# Klon.net
KiCad netlist of a schematic drawn in EAGLE
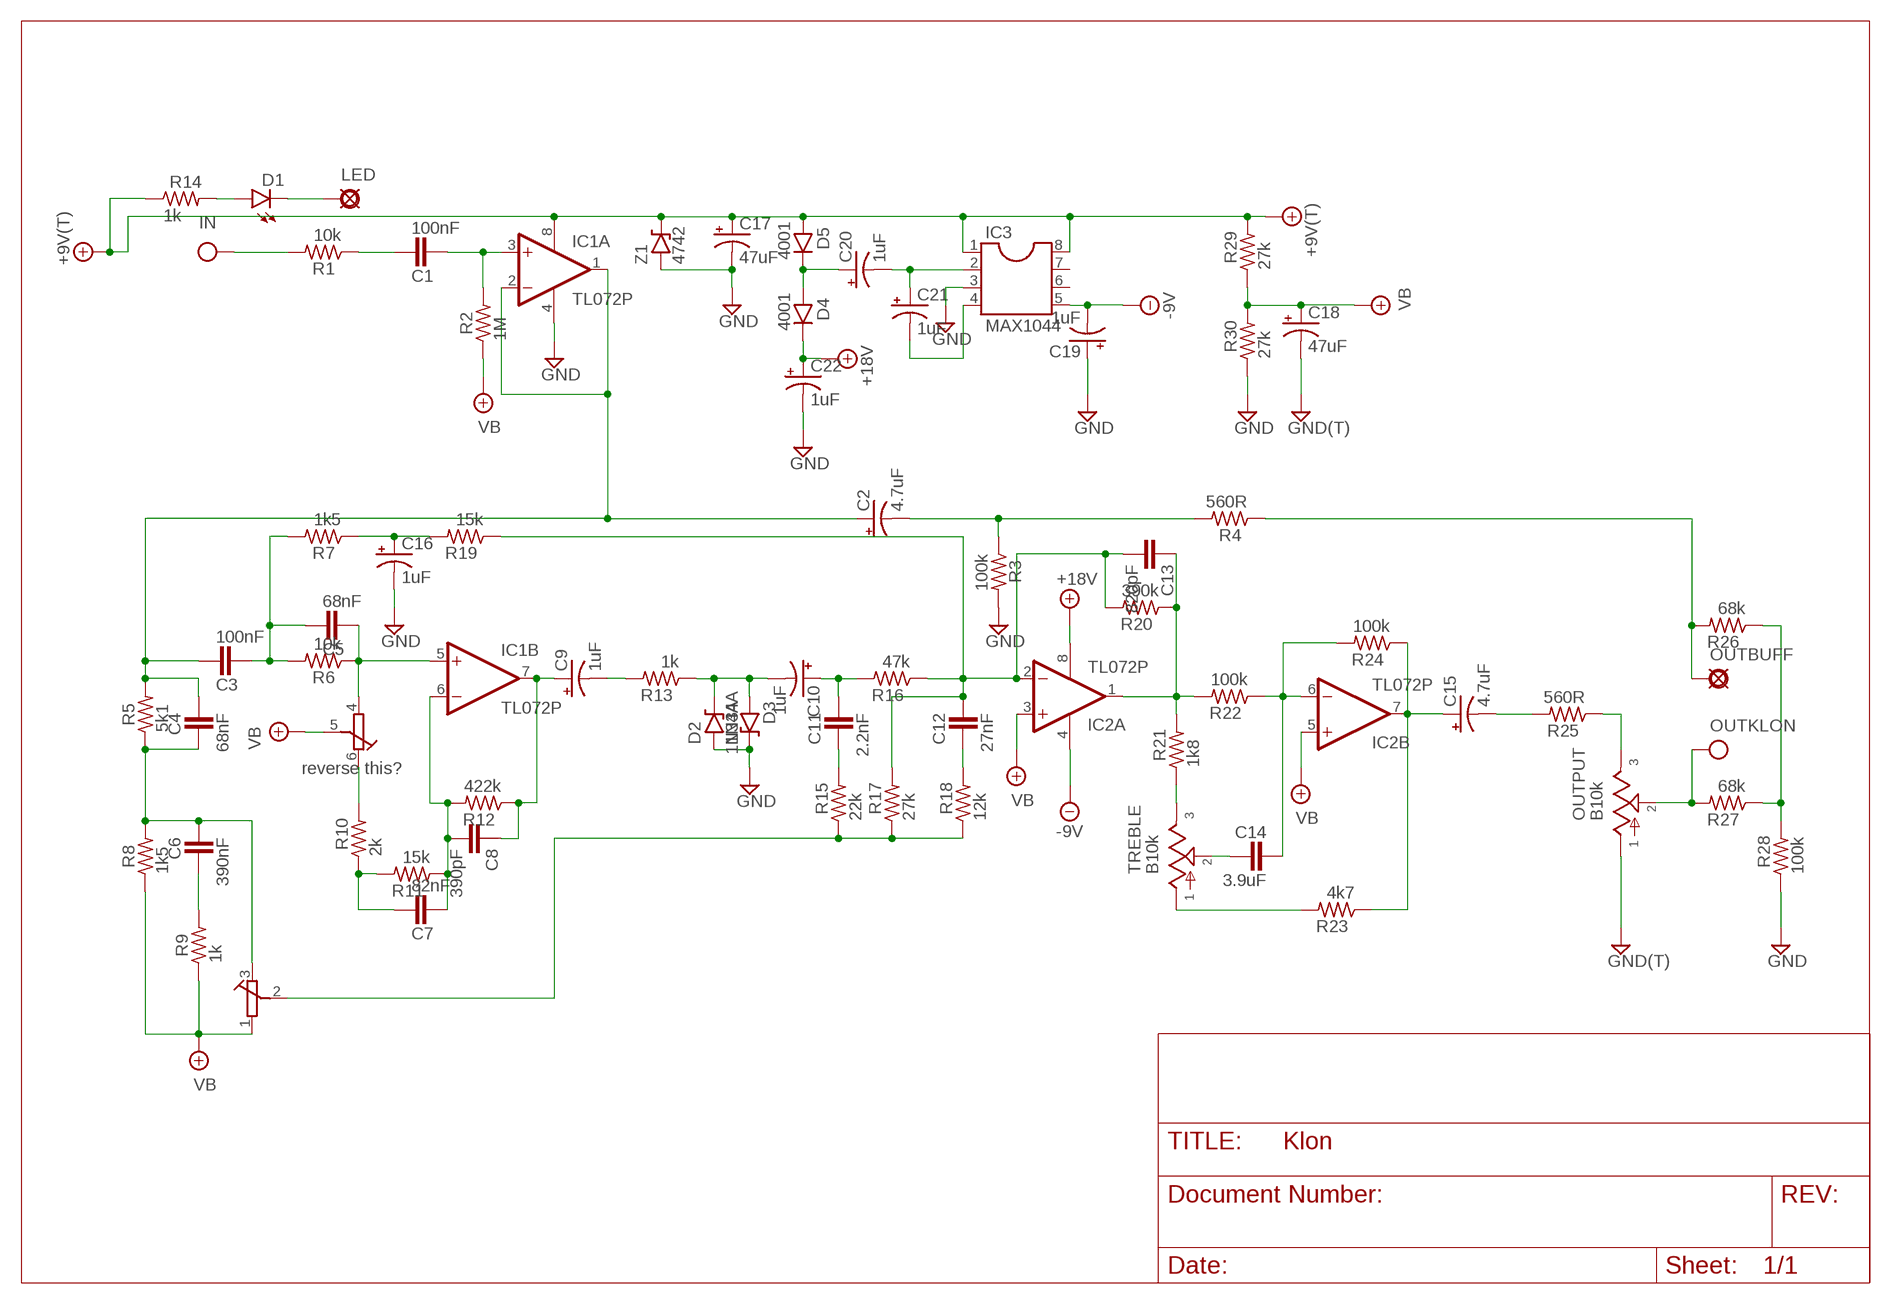
[diagram p0: schematic, sheet 1]

(export (version "E")
  (design (tool "Eeschema 10.0.6"))
  (components
    (comp (ref "+9V")
      (value "+9V(T)")
      (footprint "eagle-import:SQUARE")
      (libsource (lib "eagle-import") (part "+9V(T)"))
    )
    (comp (ref "+9V1")
      (value "+9V(T)")
      (footprint "eagle-import:SQUARE")
      (libsource (lib "eagle-import") (part "+9V(T)"))
    )
    (comp (ref "C1")
      (value "100nF")
      (footprint "eagle-import:072X025")
      (libsource (lib "eagle-import") (part "072X0252"))
    )
    (comp (ref "C2")
      (value "4.7uF")
      (footprint "eagle-import:050_020_1")
      (libsource (lib "eagle-import") (part "0501"))
    )
    (comp (ref "C3")
      (value "100nF")
      (footprint "eagle-import:072X025")
      (libsource (lib "eagle-import") (part "072X0252"))
    )
    (comp (ref "C4")
      (value "68nF")
      (footprint "eagle-import:072X025")
      (libsource (lib "eagle-import") (part "072X0252"))
    )
    (comp (ref "C5")
      (value "68nF")
      (footprint "eagle-import:072X025")
      (libsource (lib "eagle-import") (part "072X0252"))
    )
    (comp (ref "C6")
      (value "390nF")
      (footprint "eagle-import:072X025")
      (libsource (lib "eagle-import") (part "072X0252"))
    )
    (comp (ref "C7")
      (value "82nF")
      (footprint "eagle-import:072X025")
      (libsource (lib "eagle-import") (part "072X0252"))
    )
    (comp (ref "C8")
      (value "390pF")
      (footprint "eagle-import:050X030_025")
      (libsource (lib "eagle-import") (part "050X030_0251"))
    )
    (comp (ref "C9")
      (value "1uF")
      (footprint "eagle-import:050_020_1")
      (libsource (lib "eagle-import") (part "0501"))
    )
    (comp (ref "C10")
      (value "1uF")
      (footprint "eagle-import:050_020_1")
      (libsource (lib "eagle-import") (part "0501"))
    )
    (comp (ref "C11")
      (value "2.2nF")
      (footprint "eagle-import:072X025")
      (libsource (lib "eagle-import") (part "072X0252"))
    )
    (comp (ref "C12")
      (value "27nF")
      (footprint "eagle-import:072X025")
      (libsource (lib "eagle-import") (part "072X0252"))
    )
    (comp (ref "C13")
      (value "820pF")
      (footprint "eagle-import:050X030_025")
      (libsource (lib "eagle-import") (part "050X030_0251"))
    )
    (comp (ref "C14")
      (value "3.9uF")
      (footprint "eagle-import:072X025")
      (libsource (lib "eagle-import") (part "072X0252"))
    )
    (comp (ref "C15")
      (value "4.7uF")
      (footprint "eagle-import:050_020_1")
      (libsource (lib "eagle-import") (part "0501"))
    )
    (comp (ref "C16")
      (value "1uF")
      (footprint "eagle-import:050_020_1")
      (libsource (lib "eagle-import") (part "0501"))
    )
    (comp (ref "C17")
      (value "47uF")
      (footprint "eagle-import:063_025")
      (libsource (lib "eagle-import") (part "0631"))
    )
    (comp (ref "C18")
      (value "47uF")
      (footprint "eagle-import:063_025")
      (libsource (lib "eagle-import") (part "0631"))
    )
    (comp (ref "C19")
      (value "1uF")
      (footprint "eagle-import:050_020_1")
      (libsource (lib "eagle-import") (part "0501"))
    )
    (comp (ref "C20")
      (value "1uF")
      (footprint "eagle-import:050_020_1")
      (libsource (lib "eagle-import") (part "0501"))
    )
    (comp (ref "C21")
      (value "1uF")
      (footprint "eagle-import:050_020_1")
      (libsource (lib "eagle-import") (part "0501"))
    )
    (comp (ref "C22")
      (value "1uF")
      (footprint "eagle-import:050_020_1")
      (libsource (lib "eagle-import") (part "0501"))
    )
    (comp (ref "D1")
      (value "LED")
      (footprint "eagle-import:LED3MM")
      (libsource (lib "eagle-import") (part "LED3MM"))
    )
    (comp (ref "D2")
      (value "1N34A")
      (footprint "eagle-import:DO35-3")
      (libsource (lib "eagle-import") (part "1N9ZENER"))
    )
    (comp (ref "D3")
      (value "1N34A")
      (footprint "eagle-import:DO35-3")
      (libsource (lib "eagle-import") (part "1N9ZENER"))
    )
    (comp (ref "D4")
      (value "4001")
      (footprint "eagle-import:DO41-3")
      (libsource (lib "eagle-import") (part "1N400X.3"))
    )
    (comp (ref "D5")
      (value "4001")
      (footprint "eagle-import:DO41-3")
      (libsource (lib "eagle-import") (part "1N400X.3"))
    )
    (comp (ref "G")
      (value "GND(T)")
      (footprint "eagle-import:SQUARE")
      (libsource (lib "eagle-import") (part "GND(T)"))
    )
    (comp (ref "G1")
      (value "GND(T)")
      (footprint "eagle-import:SQUARE")
      (libsource (lib "eagle-import") (part "GND(T)"))
    )
    (comp (ref "GAIN")
      (value "B100k")
      (footprint "eagle-import:ALPHA16MM")
      (libsource (lib "eagle-import") (part "ALPHA16MM"))
    )
    (comp (ref "IC1")
      (value "TL072P")
      (footprint "eagle-import:DIL08")
      (libsource (lib "eagle-import") (part "TL072P"))
    )
    (comp (ref "IC2")
      (value "TL072P")
      (footprint "eagle-import:DIL08")
      (libsource (lib "eagle-import") (part "TL072P"))
    )
    (comp (ref "IC3")
      (value "MAX1044")
      (footprint "eagle-import:DIL08")
      (libsource (lib "eagle-import") (part "MAX1044"))
    )
    (comp (ref "IN")
      (value "IN(T)")
      (footprint "eagle-import:SQUARE")
      (libsource (lib "eagle-import") (part "IN(T)"))
    )
    (comp (ref "LED")
      (value "PAD")
      (footprint "eagle-import:SQUARE")
      (libsource (lib "eagle-import") (part "PAD"))
    )
    (comp (ref "OUTBUFF")
      (value "PAD")
      (footprint "eagle-import:SQUARE")
      (libsource (lib "eagle-import") (part "PAD"))
    )
    (comp (ref "OUTKLON")
      (value "OUT(T)")
      (footprint "eagle-import:SQUARE")
      (libsource (lib "eagle-import") (part "OUT(T)"))
    )
    (comp (ref "OUTPUT")
      (value "B10k")
      (footprint "eagle-import:16MM")
      (libsource (lib "eagle-import") (part "POT16MM"))
    )
    (comp (ref "R1")
      (value "10k")
      (footprint "eagle-import:R0207_3")
      (libsource (lib "eagle-import") (part "6MM.3"))
    )
    (comp (ref "R2")
      (value "1M")
      (footprint "eagle-import:R0207_3")
      (libsource (lib "eagle-import") (part "6MM.3"))
    )
    (comp (ref "R3")
      (value "100k")
      (footprint "eagle-import:R0207_3")
      (libsource (lib "eagle-import") (part "6MM.3"))
    )
    (comp (ref "R4")
      (value "560R")
      (footprint "eagle-import:R0207_3")
      (libsource (lib "eagle-import") (part "6MM.3"))
    )
    (comp (ref "R5")
      (value "5k1")
      (footprint "eagle-import:R0207_3")
      (libsource (lib "eagle-import") (part "6MM.3"))
    )
    (comp (ref "R6")
      (value "10k")
      (footprint "eagle-import:R0207_3")
      (libsource (lib "eagle-import") (part "6MM.3"))
    )
    (comp (ref "R7")
      (value "1k5")
      (footprint "eagle-import:R0207_3")
      (libsource (lib "eagle-import") (part "6MM.3"))
    )
    (comp (ref "R8")
      (value "1k5")
      (footprint "eagle-import:R0207_3")
      (libsource (lib "eagle-import") (part "6MM.3"))
    )
    (comp (ref "R9")
      (value "1k")
      (footprint "eagle-import:R0207_3")
      (libsource (lib "eagle-import") (part "6MM.3"))
    )
    (comp (ref "R10")
      (value "2k")
      (footprint "eagle-import:R0207_3")
      (libsource (lib "eagle-import") (part "6MM.3"))
    )
    (comp (ref "R11")
      (value "15k")
      (footprint "eagle-import:R0207_3")
      (libsource (lib "eagle-import") (part "6MM.3"))
    )
    (comp (ref "R12")
      (value "422k")
      (footprint "eagle-import:R0207_3")
      (libsource (lib "eagle-import") (part "6MM.3"))
    )
    (comp (ref "R13")
      (value "1k")
      (footprint "eagle-import:R0207_3")
      (libsource (lib "eagle-import") (part "6MM.3"))
    )
    (comp (ref "R14")
      (value "1k")
      (footprint "eagle-import:R0207_3")
      (libsource (lib "eagle-import") (part "6MM.3"))
    )
    (comp (ref "R15")
      (value "22k")
      (footprint "eagle-import:R0207_3")
      (libsource (lib "eagle-import") (part "6MM.3"))
    )
    (comp (ref "R16")
      (value "47k")
      (footprint "eagle-import:R0207_3")
      (libsource (lib "eagle-import") (part "6MM.3"))
    )
    (comp (ref "R17")
      (value "27k")
      (footprint "eagle-import:R0207_3")
      (libsource (lib "eagle-import") (part "6MM.3"))
    )
    (comp (ref "R18")
      (value "12k")
      (footprint "eagle-import:R0207_3")
      (libsource (lib "eagle-import") (part "6MM.3"))
    )
    (comp (ref "R19")
      (value "15k")
      (footprint "eagle-import:R0207_3")
      (libsource (lib "eagle-import") (part "6MM.3"))
    )
    (comp (ref "R20")
      (value "390k")
      (footprint "eagle-import:R0207_3")
      (libsource (lib "eagle-import") (part "6MM.3"))
    )
    (comp (ref "R21")
      (value "1k8")
      (footprint "eagle-import:R0207_3")
      (libsource (lib "eagle-import") (part "6MM.3"))
    )
    (comp (ref "R22")
      (value "100k")
      (footprint "eagle-import:R0207_3")
      (libsource (lib "eagle-import") (part "6MM.3"))
    )
    (comp (ref "R23")
      (value "4k7")
      (footprint "eagle-import:R0207_3")
      (libsource (lib "eagle-import") (part "6MM.3"))
    )
    (comp (ref "R24")
      (value "100k")
      (footprint "eagle-import:R0207_3")
      (libsource (lib "eagle-import") (part "6MM.3"))
    )
    (comp (ref "R25")
      (value "560R")
      (footprint "eagle-import:R0207_3")
      (libsource (lib "eagle-import") (part "6MM.3"))
    )
    (comp (ref "R26")
      (value "68k")
      (footprint "eagle-import:R0207_3")
      (libsource (lib "eagle-import") (part "6MM.3"))
    )
    (comp (ref "R27")
      (value "68k")
      (footprint "eagle-import:R0207_3")
      (libsource (lib "eagle-import") (part "6MM.3"))
    )
    (comp (ref "R28")
      (value "100k")
      (footprint "eagle-import:R0207_3")
      (libsource (lib "eagle-import") (part "6MM.3"))
    )
    (comp (ref "R29")
      (value "27k")
      (footprint "eagle-import:R0207_3")
      (libsource (lib "eagle-import") (part "6MM.3"))
    )
    (comp (ref "R30")
      (value "27k")
      (footprint "eagle-import:R0207_3")
      (libsource (lib "eagle-import") (part "6MM.3"))
    )
    (comp (ref "TREBLE")
      (value "B10k")
      (footprint "eagle-import:16MM")
      (libsource (lib "eagle-import") (part "POT16MM"))
    )
    (comp (ref "Z1")
      (value "4742")
      (footprint "eagle-import:DO41-3")
      (libsource (lib "eagle-import") (part "1N47XX3"))
    )
  )
  (nets
    (net (code "1") (name "+9V(T)") (class "Default")
      (node (ref "+9V") (pin "1") (pinfunction "+9V_1") (pintype "power_in"))
      (node (ref "+9V1") (pin "1") (pinfunction "+9V_1") (pintype "power_in"))
      (node (ref "C17") (pin "+") (pinfunction "+_+") (pintype "passive"))
      (node (ref "D5") (pin "A") (pinfunction "A_A") (pintype "passive"))
      (node (ref "IC1") (pin "8") (pinfunction "V+_8") (pintype "power_in"))
      (node (ref "IC3") (pin "1") (pinfunction "1_1") (pintype "passive"))
      (node (ref "IC3") (pin "8") (pinfunction "8_8") (pintype "passive"))
      (node (ref "R14") (pin "1") (pinfunction "1_1") (pintype "passive"))
      (node (ref "R29") (pin "2") (pinfunction "2_2") (pintype "passive"))
      (node (ref "Z1") (pin "C") (pinfunction "C_C") (pintype "passive"))
    )
    (net (code "2") (name "+18V") (class "Default")
      (node (ref "C22") (pin "+") (pinfunction "+_+") (pintype "passive"))
      (node (ref "D4") (pin "C") (pinfunction "C_C") (pintype "passive"))
      (node (ref "IC2") (pin "8") (pinfunction "V+_8") (pintype "power_in"))
    )
    (net (code "3") (name "-9V") (class "Default")
      (node (ref "C19") (pin "-") (pinfunction "-_-") (pintype "passive"))
      (node (ref "IC2") (pin "4") (pinfunction "V-_4") (pintype "power_in"))
      (node (ref "IC3") (pin "5") (pinfunction "5_5") (pintype "passive"))
    )
    (net (code "4") (name "GND") (class "Default")
      (node (ref "C16") (pin "-") (pinfunction "-_-") (pintype "passive"))
      (node (ref "C17") (pin "-") (pinfunction "-_-") (pintype "passive"))
      (node (ref "C18") (pin "-") (pinfunction "-_-") (pintype "passive"))
      (node (ref "C19") (pin "+") (pinfunction "+_+") (pintype "passive"))
      (node (ref "C22") (pin "-") (pinfunction "-_-") (pintype "passive"))
      (node (ref "D2") (pin "A") (pinfunction "A_A") (pintype "passive"))
      (node (ref "D3") (pin "C") (pinfunction "C_C") (pintype "passive"))
      (node (ref "G") (pin "1") (pinfunction "GND_1") (pintype "power_in"))
      (node (ref "G1") (pin "1") (pinfunction "GND_1") (pintype "power_in"))
      (node (ref "IC1") (pin "4") (pinfunction "V-_4") (pintype "power_in"))
      (node (ref "IC3") (pin "3") (pinfunction "3_3") (pintype "passive"))
      (node (ref "OUTPUT") (pin "1") (pinfunction "1_1") (pintype "passive"))
      (node (ref "R28") (pin "1") (pinfunction "1_1") (pintype "passive"))
      (node (ref "R3") (pin "2") (pinfunction "2_2") (pintype "passive"))
      (node (ref "R30") (pin "1") (pinfunction "1_1") (pintype "passive"))
      (node (ref "Z1") (pin "A") (pinfunction "A_A") (pintype "passive"))
    )
    (net (code "5") (name "IN(T)") (class "Default")
      (node (ref "IN") (pin "1") (pinfunction "IN_1") (pintype "power_in"))
      (node (ref "R1") (pin "2") (pinfunction "2_2") (pintype "passive"))
    )
    (net (code "6") (name "Net-(C1-Pad2)") (class "Default")
      (node (ref "C1") (pin "2") (pinfunction "2_2") (pintype "passive"))
      (node (ref "R1") (pin "1") (pinfunction "1_1") (pintype "passive"))
    )
    (net (code "7") (name "Net-(C2-Pad-)") (class "Default")
      (node (ref "C2") (pin "-") (pinfunction "-_-") (pintype "passive"))
      (node (ref "R3") (pin "1") (pinfunction "1_1") (pintype "passive"))
      (node (ref "R4") (pin "2") (pinfunction "2_2") (pintype "passive"))
    )
    (net (code "8") (name "Net-(C3-Pad1)") (class "Default")
      (node (ref "C3") (pin "1") (pinfunction "1_1") (pintype "passive"))
      (node (ref "C5") (pin "2") (pinfunction "2_2") (pintype "passive"))
      (node (ref "R6") (pin "2") (pinfunction "2_2") (pintype "passive"))
      (node (ref "R7") (pin "2") (pinfunction "2_2") (pintype "passive"))
    )
    (net (code "9") (name "Net-(C6-Pad1)") (class "Default")
      (node (ref "C6") (pin "1") (pinfunction "1_1") (pintype "passive"))
      (node (ref "R9") (pin "2") (pinfunction "2_2") (pintype "passive"))
    )
    (net (code "10") (name "Net-(C7-Pad2)") (class "Default")
      (node (ref "C7") (pin "2") (pinfunction "2_2") (pintype "passive"))
      (node (ref "R10") (pin "1") (pinfunction "1_1") (pintype "passive"))
      (node (ref "R11") (pin "2") (pinfunction "2_2") (pintype "passive"))
    )
    (net (code "11") (name "Net-(C9-Pad-)") (class "Default")
      (node (ref "C9") (pin "-") (pinfunction "-_-") (pintype "passive"))
      (node (ref "R13") (pin "2") (pinfunction "2_2") (pintype "passive"))
    )
    (net (code "12") (name "Net-(C10-Pad+)") (class "Default")
      (node (ref "C10") (pin "+") (pinfunction "+_+") (pintype "passive"))
      (node (ref "C11") (pin "2") (pinfunction "2_2") (pintype "passive"))
      (node (ref "R16") (pin "2") (pinfunction "2_2") (pintype "passive"))
    )
    (net (code "13") (name "Net-(C10-Pad-)") (class "Default")
      (node (ref "C10") (pin "-") (pinfunction "-_-") (pintype "passive"))
      (node (ref "D2") (pin "C") (pinfunction "C_C") (pintype "passive"))
      (node (ref "D3") (pin "A") (pinfunction "A_A") (pintype "passive"))
      (node (ref "R13") (pin "1") (pinfunction "1_1") (pintype "passive"))
    )
    (net (code "14") (name "Net-(C11-Pad1)") (class "Default")
      (node (ref "C11") (pin "1") (pinfunction "1_1") (pintype "passive"))
      (node (ref "R15") (pin "2") (pinfunction "2_2") (pintype "passive"))
    )
    (net (code "15") (name "Net-(C12-Pad1)") (class "Default")
      (node (ref "C12") (pin "1") (pinfunction "1_1") (pintype "passive"))
      (node (ref "R18") (pin "2") (pinfunction "2_2") (pintype "passive"))
    )
    (net (code "16") (name "Net-(C14-Pad1)") (class "Default")
      (node (ref "C14") (pin "1") (pinfunction "1_1") (pintype "passive"))
      (node (ref "TREBLE") (pin "2") (pinfunction "2_2") (pintype "passive"))
    )
    (net (code "17") (name "Net-(C15-Pad-)") (class "Default")
      (node (ref "C15") (pin "-") (pinfunction "-_-") (pintype "passive"))
      (node (ref "R25") (pin "2") (pinfunction "2_2") (pintype "passive"))
    )
    (net (code "18") (name "Net-(C16-Pad+)") (class "Default")
      (node (ref "C16") (pin "+") (pinfunction "+_+") (pintype "passive"))
      (node (ref "R19") (pin "2") (pinfunction "2_2") (pintype "passive"))
      (node (ref "R7") (pin "1") (pinfunction "1_1") (pintype "passive"))
    )
    (net (code "19") (name "Net-(C20-Pad+)") (class "Default")
      (node (ref "C20") (pin "+") (pinfunction "+_+") (pintype "passive"))
      (node (ref "D4") (pin "A") (pinfunction "A_A") (pintype "passive"))
      (node (ref "D5") (pin "C") (pinfunction "C_C") (pintype "passive"))
    )
    (net (code "20") (name "Net-(C20-Pad-)") (class "Default")
      (node (ref "C20") (pin "-") (pinfunction "-_-") (pintype "passive"))
      (node (ref "C21") (pin "+") (pinfunction "+_+") (pintype "passive"))
      (node (ref "IC3") (pin "2") (pinfunction "2_2") (pintype "passive"))
    )
    (net (code "21") (name "Net-(C21-Pad-)") (class "Default")
      (node (ref "C21") (pin "-") (pinfunction "-_-") (pintype "passive"))
      (node (ref "IC3") (pin "4") (pinfunction "4_4") (pintype "passive"))
    )
    (net (code "22") (name "Net-(D1-C)") (class "Default")
      (node (ref "D1") (pin "K") (pinfunction "C_K") (pintype "passive"))
      (node (ref "LED") (pin "1") (pinfunction "PAD_1") (pintype "passive"))
    )
    (net (code "23") (name "Net-(D1-PadA)") (class "Default")
      (node (ref "D1") (pin "A") (pinfunction "A_A") (pintype "passive"))
      (node (ref "R14") (pin "2") (pinfunction "2_2") (pintype "passive"))
    )
    (net (code "24") (name "Net-(GAINA-IN)") (class "Default")
      (node (ref "C4") (pin "1") (pinfunction "1_1") (pintype "passive"))
      (node (ref "C6") (pin "2") (pinfunction "2_2") (pintype "passive"))
      (node (ref "GAIN") (pin "3") (pinfunction "IN_3") (pintype "bidirectional"))
      (node (ref "R5") (pin "1") (pinfunction "1_1") (pintype "passive"))
      (node (ref "R8") (pin "2") (pinfunction "2_2") (pintype "passive"))
    )
    (net (code "25") (name "Net-(GAINA-OUT)") (class "Default")
      (node (ref "GAIN") (pin "2") (pinfunction "OUT_2") (pintype "bidirectional"))
      (node (ref "R15") (pin "1") (pinfunction "1_1") (pintype "passive"))
      (node (ref "R17") (pin "1") (pinfunction "1_1") (pintype "passive"))
      (node (ref "R18") (pin "1") (pinfunction "1_1") (pintype "passive"))
    )
    (net (code "26") (name "Net-(GAINB-GND)") (class "Default")
      (node (ref "C5") (pin "1") (pinfunction "1_1") (pintype "passive"))
      (node (ref "GAIN") (pin "4") (pinfunction "GND_4") (pintype "bidirectional"))
      (node (ref "IC1") (pin "5") (pinfunction "+IN_5") (pintype "input"))
      (node (ref "R6") (pin "1") (pinfunction "1_1") (pintype "passive"))
    )
    (net (code "27") (name "Net-(GAINB-IN)") (class "Default")
      (node (ref "GAIN") (pin "6") (pinfunction "IN_6") (pintype "bidirectional"))
      (node (ref "R10") (pin "2") (pinfunction "2_2") (pintype "passive"))
    )
    (net (code "28") (name "Net-(IC1A-+IN)") (class "Default")
      (node (ref "C1") (pin "1") (pinfunction "1_1") (pintype "passive"))
      (node (ref "IC1") (pin "3") (pinfunction "+IN_3") (pintype "input"))
      (node (ref "R2") (pin "2") (pinfunction "2_2") (pintype "passive"))
    )
    (net (code "29") (name "Net-(IC1A--IN)") (class "Default")
      (node (ref "C2") (pin "+") (pinfunction "+_+") (pintype "passive"))
      (node (ref "C3") (pin "2") (pinfunction "2_2") (pintype "passive"))
      (node (ref "C4") (pin "2") (pinfunction "2_2") (pintype "passive"))
      (node (ref "IC1") (pin "1") (pinfunction "OUT_1") (pintype "output"))
      (node (ref "IC1") (pin "2") (pinfunction "-IN_2") (pintype "input"))
      (node (ref "R5") (pin "2") (pinfunction "2_2") (pintype "passive"))
    )
    (net (code "30") (name "Net-(IC1B--IN)") (class "Default")
      (node (ref "C7") (pin "1") (pinfunction "1_1") (pintype "passive"))
      (node (ref "C8") (pin "2") (pinfunction "2_2") (pintype "passive"))
      (node (ref "IC1") (pin "6") (pinfunction "-IN_6") (pintype "input"))
      (node (ref "R11") (pin "1") (pinfunction "1_1") (pintype "passive"))
      (node (ref "R12") (pin "2") (pinfunction "2_2") (pintype "passive"))
    )
    (net (code "31") (name "Net-(IC1B-OUT)") (class "Default")
      (node (ref "C8") (pin "1") (pinfunction "1_1") (pintype "passive"))
      (node (ref "C9") (pin "+") (pinfunction "+_+") (pintype "passive"))
      (node (ref "IC1") (pin "7") (pinfunction "OUT_7") (pintype "output"))
      (node (ref "R12") (pin "1") (pinfunction "1_1") (pintype "passive"))
    )
    (net (code "32") (name "Net-(IC2A--IN)") (class "Default")
      (node (ref "C12") (pin "2") (pinfunction "2_2") (pintype "passive"))
      (node (ref "C13") (pin "2") (pinfunction "2_2") (pintype "passive"))
      (node (ref "IC2") (pin "2") (pinfunction "-IN_2") (pintype "input"))
      (node (ref "R16") (pin "1") (pinfunction "1_1") (pintype "passive"))
      (node (ref "R17") (pin "2") (pinfunction "2_2") (pintype "passive"))
      (node (ref "R19") (pin "1") (pinfunction "1_1") (pintype "passive"))
      (node (ref "R20") (pin "2") (pinfunction "2_2") (pintype "passive"))
    )
    (net (code "33") (name "Net-(IC2A-OUT)") (class "Default")
      (node (ref "C13") (pin "1") (pinfunction "1_1") (pintype "passive"))
      (node (ref "IC2") (pin "1") (pinfunction "OUT_1") (pintype "output"))
      (node (ref "R20") (pin "1") (pinfunction "1_1") (pintype "passive"))
      (node (ref "R21") (pin "2") (pinfunction "2_2") (pintype "passive"))
      (node (ref "R22") (pin "2") (pinfunction "2_2") (pintype "passive"))
    )
    (net (code "34") (name "Net-(IC2B--IN)") (class "Default")
      (node (ref "C14") (pin "2") (pinfunction "2_2") (pintype "passive"))
      (node (ref "IC2") (pin "6") (pinfunction "-IN_6") (pintype "input"))
      (node (ref "R22") (pin "1") (pinfunction "1_1") (pintype "passive"))
      (node (ref "R24") (pin "2") (pinfunction "2_2") (pintype "passive"))
    )
    (net (code "35") (name "Net-(IC2B-OUT)") (class "Default")
      (node (ref "C15") (pin "+") (pinfunction "+_+") (pintype "passive"))
      (node (ref "IC2") (pin "7") (pinfunction "OUT_7") (pintype "output"))
      (node (ref "R23") (pin "1") (pinfunction "1_1") (pintype "passive"))
      (node (ref "R24") (pin "1") (pinfunction "1_1") (pintype "passive"))
    )
    (net (code "36") (name "Net-(OUTBUFF-PAD)") (class "Default")
      (node (ref "OUTBUFF") (pin "1") (pinfunction "PAD_1") (pintype "passive"))
      (node (ref "R26") (pin "2") (pinfunction "2_2") (pintype "passive"))
      (node (ref "R4") (pin "1") (pinfunction "1_1") (pintype "passive"))
    )
    (net (code "37") (name "Net-(OUTPUT-Pad3)") (class "Default")
      (node (ref "OUTPUT") (pin "3") (pinfunction "3_3") (pintype "passive"))
      (node (ref "R25") (pin "1") (pinfunction "1_1") (pintype "passive"))
    )
    (net (code "38") (name "Net-(R21-Pad1)") (class "Default")
      (node (ref "R21") (pin "1") (pinfunction "1_1") (pintype "passive"))
      (node (ref "TREBLE") (pin "3") (pinfunction "3_3") (pintype "passive"))
    )
    (net (code "39") (name "Net-(R23-Pad2)") (class "Default")
      (node (ref "R23") (pin "2") (pinfunction "2_2") (pintype "passive"))
      (node (ref "TREBLE") (pin "1") (pinfunction "1_1") (pintype "passive"))
    )
    (net (code "40") (name "Net-(R26-Pad1)") (class "Default")
      (node (ref "R26") (pin "1") (pinfunction "1_1") (pintype "passive"))
      (node (ref "R27") (pin "1") (pinfunction "1_1") (pintype "passive"))
      (node (ref "R28") (pin "2") (pinfunction "2_2") (pintype "passive"))
    )
    (net (code "41") (name "OUT(T)") (class "Default")
      (node (ref "OUTKLON") (pin "1") (pinfunction "OUT_1") (pintype "power_in"))
      (node (ref "OUTPUT") (pin "2") (pinfunction "2_2") (pintype "passive"))
      (node (ref "R27") (pin "2") (pinfunction "2_2") (pintype "passive"))
    )
    (net (code "42") (name "VB") (class "Default")
      (node (ref "C18") (pin "+") (pinfunction "+_+") (pintype "passive"))
      (node (ref "GAIN") (pin "1") (pinfunction "GND_1") (pintype "bidirectional"))
      (node (ref "GAIN") (pin "5") (pinfunction "OUT_5") (pintype "bidirectional"))
      (node (ref "IC2") (pin "3") (pinfunction "+IN_3") (pintype "input"))
      (node (ref "IC2") (pin "5") (pinfunction "+IN_5") (pintype "input"))
      (node (ref "R2") (pin "1") (pinfunction "1_1") (pintype "passive"))
      (node (ref "R29") (pin "1") (pinfunction "1_1") (pintype "passive"))
      (node (ref "R30") (pin "2") (pinfunction "2_2") (pintype "passive"))
      (node (ref "R8") (pin "1") (pinfunction "1_1") (pintype "passive"))
      (node (ref "R9") (pin "1") (pinfunction "1_1") (pintype "passive"))
    )
    (net (code "43") (name "unconnected-(IC3-Pad6)") (class "Default")
      (node (ref "IC3") (pin "6") (pinfunction "6_6") (pintype "passive"))
    )
    (net (code "44") (name "unconnected-(IC3-Pad7)") (class "Default")
      (node (ref "IC3") (pin "7") (pinfunction "7_7") (pintype "passive"))
    )
  )
)
